# MCU.net
KiCad netlist of a schematic drawn in Altium Designer
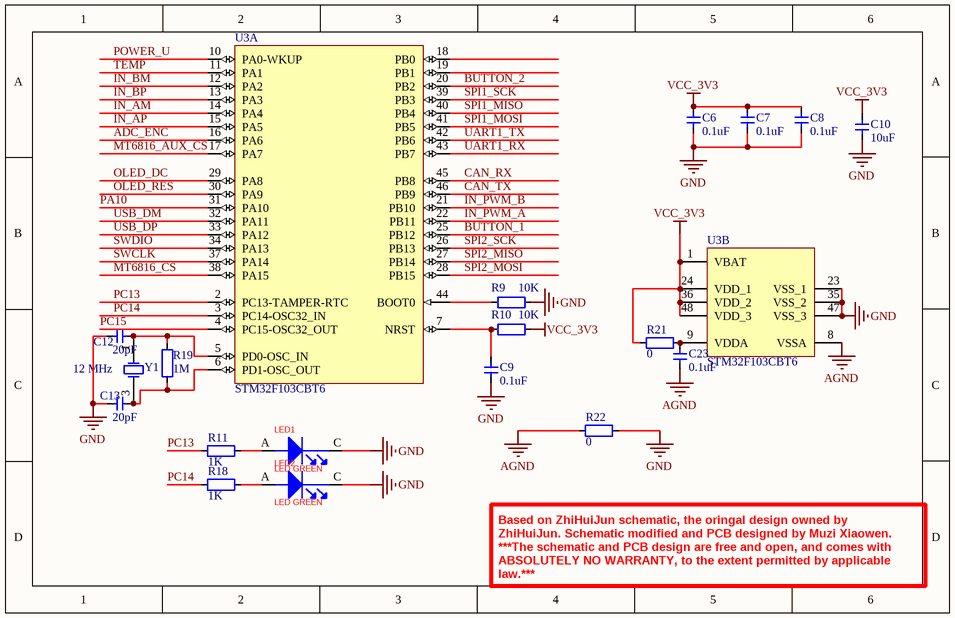
[diagram p0: MCU.SchDoc]

(export (version "E")
  (design (tool "Eeschema 10.0.6"))
  (components
    (comp (ref "C6")
      (value "0.1uF")
      (footprint "motor42-lib:CAP_0402")
      (description "Capacitor")
      (libsource (lib "MyPcbLib") (part "电容-0402"))
    )
    (comp (ref "C7")
      (value "0.1uF")
      (footprint "motor42-lib:CAP_0402")
      (description "Capacitor")
      (libsource (lib "MyPcbLib") (part "电容-0402"))
    )
    (comp (ref "C8")
      (value "0.1uF")
      (footprint "motor42-lib:CAP_0402")
      (description "Capacitor")
      (libsource (lib "MyPcbLib") (part "电容-0402"))
    )
    (comp (ref "C9")
      (value "0.1uF")
      (footprint "motor42-lib:CAP_0402")
      (description "Capacitor")
      (libsource (lib "MyPcbLib") (part "电容-0402"))
    )
    (comp (ref "C10")
      (value "10uF")
      (footprint "CAP_0402")
      (description "Capacitor")
      (libsource (lib "MyPcbLib") (part "电容-0402"))
    )
    (comp (ref "C12")
      (value "20pF")
      (footprint "motor42-lib:CAP_0402")
      (description "Capacitor")
      (libsource (lib "MyPcbLib") (part "电容-0402"))
    )
    (comp (ref "C13")
      (value "20pF")
      (footprint "motor42-lib:CAP_0402")
      (description "Capacitor")
      (libsource (lib "MyPcbLib") (part "电容-0402"))
    )
    (comp (ref "C23")
      (value "0.1uF")
      (footprint "motor42-lib:CAP_0402")
      (description "Capacitor")
      (libsource (lib "MyPcbLib") (part "电容-0402"))
    )
    (comp (ref "LED1")
      (value "LED GREEN")
      (footprint "LED-0603")
      (description "LED GRN SGL RA 25mA 4.1V SMD")
      (libsource (lib "*") (part "LED"))
    )
    (comp (ref "LED2")
      (value "LED GREEN")
      (footprint "LED-0603")
      (description "LED GRN SGL RA 25mA 4.1V SMD")
      (libsource (lib "*") (part "LED"))
    )
    (comp (ref "R9")
      (value "10K")
      (footprint "RES_0402")
      (description "Resistor")
      (libsource (lib "MyPcbLib") (part "电阻-0402"))
    )
    (comp (ref "R10")
      (value "10K")
      (footprint "RES_0402")
      (description "Resistor")
      (libsource (lib "MyPcbLib") (part "电阻-0402"))
    )
    (comp (ref "R11")
      (value "1K")
      (footprint "RES_0402")
      (description "Resistor")
      (libsource (lib "MyPcbLib") (part "电阻-0402"))
    )
    (comp (ref "R18")
      (value "1K")
      (footprint "RES_0402")
      (description "Resistor")
      (libsource (lib "MyPcbLib") (part "电阻-0402"))
    )
    (comp (ref "R19")
      (value "1M")
      (footprint "RES_0402")
      (description "Resistor")
      (libsource (lib "") (part "电阻-0402_2"))
    )
    (comp (ref "R21")
      (value "0")
      (footprint "RES_0402")
      (description "Resistor")
      (libsource (lib "") (part "电阻-0402_1"))
    )
    (comp (ref "R22")
      (value "0")
      (footprint "RES_0402")
      (description "Resistor")
      (libsource (lib "") (part "电阻-0402_1"))
    )
    (comp (ref "U3")
      (value "STM32F103CBT6")
      (footprint "motor42-lib:LQFP-48")
      (libsource (lib "STMicroelectronics STM32 F1") (part "STM32F103CBT6"))
    )
    (comp (ref "Y1")
      (value "12 MHz")
      (footprint "LC-SMD-3225_4P")
      (description "Crystal")
      (fields (field (name "Comment") "XTAL-4"))
      (libsource (lib "rpi") (part "XTAL-4"))
    )
  )
  (nets
    (net (code "1") (name "/ADC_ENC") (class "Default")
      (node (ref "U3") (pin "16") (pinfunction "PA6_16") (pintype "bidirectional"))
    )
    (net (code "2") (name "/BUTTON_1") (class "Default")
      (node (ref "U3") (pin "25") (pinfunction "PB12_25") (pintype "bidirectional"))
    )
    (net (code "3") (name "/BUTTON_2") (class "Default")
      (node (ref "U3") (pin "20") (pinfunction "PB2_20") (pintype "bidirectional"))
    )
    (net (code "4") (name "/CAN_RX") (class "Default")
      (node (ref "U3") (pin "45") (pinfunction "PB8_45") (pintype "bidirectional"))
    )
    (net (code "5") (name "/CAN_TX") (class "Default")
      (node (ref "U3") (pin "46") (pinfunction "PB9_46") (pintype "bidirectional"))
    )
    (net (code "6") (name "/IN_AM") (class "Default")
      (node (ref "U3") (pin "14") (pinfunction "PA4_14") (pintype "bidirectional"))
    )
    (net (code "7") (name "/IN_AP") (class "Default")
      (node (ref "U3") (pin "15") (pinfunction "PA5_15") (pintype "bidirectional"))
    )
    (net (code "8") (name "/IN_BM") (class "Default")
      (node (ref "U3") (pin "12") (pinfunction "PA2_12") (pintype "bidirectional"))
    )
    (net (code "9") (name "/IN_BP") (class "Default")
      (node (ref "U3") (pin "13") (pinfunction "PA3_13") (pintype "bidirectional"))
    )
    (net (code "10") (name "/IN_PWM_A") (class "Default")
      (node (ref "U3") (pin "22") (pinfunction "PB11_22") (pintype "bidirectional"))
    )
    (net (code "11") (name "/IN_PWM_B") (class "Default")
      (node (ref "U3") (pin "21") (pinfunction "PB10_21") (pintype "bidirectional"))
    )
    (net (code "12") (name "/MT6816_AUX_CS") (class "Default")
      (node (ref "U3") (pin "17") (pinfunction "PA7_17") (pintype "bidirectional"))
    )
    (net (code "13") (name "/MT6816_CS") (class "Default")
      (node (ref "U3") (pin "38") (pinfunction "PA15_38") (pintype "bidirectional"))
    )
    (net (code "14") (name "/OLED_DC") (class "Default")
      (node (ref "U3") (pin "29") (pinfunction "PA8_29") (pintype "bidirectional"))
    )
    (net (code "15") (name "/OLED_RES") (class "Default")
      (node (ref "U3") (pin "30") (pinfunction "PA9_30") (pintype "bidirectional"))
    )
    (net (code "16") (name "/PA10") (class "Default")
      (node (ref "U3") (pin "31") (pinfunction "PA10_31") (pintype "bidirectional"))
    )
    (net (code "17") (name "/PC13") (class "Default")
      (node (ref "R11") (pin "1") (pinfunction "1_1") (pintype "passive"))
      (node (ref "U3") (pin "2") (pinfunction "PC13-TAMPER-RTC_2") (pintype "bidirectional"))
    )
    (net (code "18") (name "/PC14") (class "Default")
      (node (ref "R18") (pin "1") (pinfunction "1_1") (pintype "passive"))
      (node (ref "U3") (pin "3") (pinfunction "PC14-OSC32_IN_3") (pintype "bidirectional"))
    )
    (net (code "19") (name "/PC15") (class "Default")
      (node (ref "U3") (pin "4") (pinfunction "PC15-OSC32_OUT_4") (pintype "bidirectional"))
    )
    (net (code "20") (name "/POWER_U") (class "Default")
      (node (ref "U3") (pin "10") (pinfunction "PA0-WKUP_10") (pintype "bidirectional"))
    )
    (net (code "21") (name "/SPI1_MISO") (class "Default")
      (node (ref "U3") (pin "40") (pinfunction "PB4_40") (pintype "bidirectional"))
    )
    (net (code "22") (name "/SPI1_MOSI") (class "Default")
      (node (ref "U3") (pin "41") (pinfunction "PB5_41") (pintype "bidirectional"))
    )
    (net (code "23") (name "/SPI1_SCK") (class "Default")
      (node (ref "U3") (pin "39") (pinfunction "PB3_39") (pintype "bidirectional"))
    )
    (net (code "24") (name "/SPI2_MISO") (class "Default")
      (node (ref "U3") (pin "27") (pinfunction "PB14_27") (pintype "bidirectional"))
    )
    (net (code "25") (name "/SPI2_MOSI") (class "Default")
      (node (ref "U3") (pin "28") (pinfunction "PB15_28") (pintype "bidirectional"))
    )
    (net (code "26") (name "/SPI2_SCK") (class "Default")
      (node (ref "U3") (pin "26") (pinfunction "PB13_26") (pintype "bidirectional"))
    )
    (net (code "27") (name "/SWCLK") (class "Default")
      (node (ref "U3") (pin "37") (pinfunction "PA14_37") (pintype "bidirectional"))
    )
    (net (code "28") (name "/SWDIO") (class "Default")
      (node (ref "U3") (pin "34") (pinfunction "PA13_34") (pintype "bidirectional"))
    )
    (net (code "29") (name "/TEMP") (class "Default")
      (node (ref "U3") (pin "11") (pinfunction "PA1_11") (pintype "bidirectional"))
    )
    (net (code "30") (name "/UART1_RX") (class "Default")
      (node (ref "U3") (pin "43") (pinfunction "PB7_43") (pintype "bidirectional"))
    )
    (net (code "31") (name "/UART1_TX") (class "Default")
      (node (ref "U3") (pin "42") (pinfunction "PB6_42") (pintype "bidirectional"))
    )
    (net (code "32") (name "/USB_DM") (class "Default")
      (node (ref "U3") (pin "32") (pinfunction "PA11_32") (pintype "bidirectional"))
    )
    (net (code "33") (name "/USB_DP") (class "Default")
      (node (ref "U3") (pin "33") (pinfunction "PA12_33") (pintype "bidirectional"))
    )
    (net (code "34") (name "AGND") (class "Default")
      (node (ref "C23") (pin "1") (pinfunction "1_1") (pintype "passive"))
      (node (ref "R22") (pin "2") (pinfunction "2_2") (pintype "passive"))
      (node (ref "U3") (pin "8") (pinfunction "VSSA_8") (pintype "power_in"))
    )
    (net (code "35") (name "GND") (class "Default")
      (node (ref "C10") (pin "1") (pinfunction "1_1") (pintype "passive"))
      (node (ref "C12") (pin "2") (pinfunction "2_2") (pintype "passive"))
      (node (ref "C13") (pin "2") (pinfunction "2_2") (pintype "passive"))
      (node (ref "C6") (pin "1") (pinfunction "1_1") (pintype "passive"))
      (node (ref "C7") (pin "1") (pinfunction "1_1") (pintype "passive"))
      (node (ref "C8") (pin "1") (pinfunction "1_1") (pintype "passive"))
      (node (ref "C9") (pin "1") (pinfunction "1_1") (pintype "passive"))
      (node (ref "LED1") (pin "C") (pinfunction "CATHODE_C") (pintype "passive"))
      (node (ref "LED2") (pin "C") (pinfunction "CATHODE_C") (pintype "passive"))
      (node (ref "R22") (pin "1") (pinfunction "1_1") (pintype "passive"))
      (node (ref "R9") (pin "2") (pinfunction "2_2") (pintype "passive"))
      (node (ref "U3") (pin "23") (pinfunction "VSS_1_23") (pintype "power_in"))
      (node (ref "U3") (pin "35") (pinfunction "VSS_2_35") (pintype "power_in"))
      (node (ref "U3") (pin "47") (pinfunction "VSS_3_47") (pintype "power_in"))
    )
    (net (code "36") (name "Net-(LED1-ANODE)") (class "Default")
      (node (ref "LED1") (pin "A") (pinfunction "ANODE_A") (pintype "passive"))
      (node (ref "R11") (pin "2") (pinfunction "2_2") (pintype "passive"))
    )
    (net (code "37") (name "Net-(LED2-ANODE)") (class "Default")
      (node (ref "LED2") (pin "A") (pinfunction "ANODE_A") (pintype "passive"))
      (node (ref "R18") (pin "2") (pinfunction "2_2") (pintype "passive"))
    )
    (net (code "38") (name "Net-(U3A-BOOT0)") (class "Default")
      (node (ref "R9") (pin "1") (pinfunction "1_1") (pintype "passive"))
      (node (ref "U3") (pin "44") (pinfunction "BOOT0_44") (pintype "input"))
    )
    (net (code "39") (name "Net-(U3A-NRST)") (class "Default")
      (node (ref "C9") (pin "2") (pinfunction "2_2") (pintype "passive"))
      (node (ref "R10") (pin "1") (pinfunction "1_1") (pintype "passive"))
      (node (ref "U3") (pin "7") (pinfunction "NRST_7") (pintype "bidirectional"))
    )
    (net (code "40") (name "Net-(U3A-PD0-OSC_IN)") (class "Default")
      (node (ref "C12") (pin "1") (pinfunction "1_1") (pintype "passive"))
      (node (ref "R19") (pin "2") (pinfunction "2_2") (pintype "passive"))
      (node (ref "U3") (pin "5") (pinfunction "PD0-OSC_IN_5") (pintype "bidirectional"))
      (node (ref "Y1") (pin "1") (pinfunction "OSC1_1") (pintype "passive"))
    )
    (net (code "41") (name "Net-(U3A-PD1-OSC_OUT)") (class "Default")
      (node (ref "C13") (pin "1") (pinfunction "1_1") (pintype "passive"))
      (node (ref "R19") (pin "1") (pinfunction "1_1") (pintype "passive"))
      (node (ref "U3") (pin "6") (pinfunction "PD1-OSC_OUT_6") (pintype "bidirectional"))
      (node (ref "Y1") (pin "3") (pinfunction "OSC2_3") (pintype "passive"))
    )
    (net (code "42") (name "Net-(U3B-VDDA)") (class "Default")
      (node (ref "C23") (pin "2") (pinfunction "2_2") (pintype "passive"))
      (node (ref "R21") (pin "1") (pinfunction "1_1") (pintype "passive"))
      (node (ref "U3") (pin "9") (pinfunction "VDDA_9") (pintype "power_in"))
    )
    (net (code "43") (name "VCC_3V3") (class "Default")
      (node (ref "C10") (pin "2") (pinfunction "2_2") (pintype "passive"))
      (node (ref "C6") (pin "2") (pinfunction "2_2") (pintype "passive"))
      (node (ref "C7") (pin "2") (pinfunction "2_2") (pintype "passive"))
      (node (ref "C8") (pin "2") (pinfunction "2_2") (pintype "passive"))
      (node (ref "R10") (pin "2") (pinfunction "2_2") (pintype "passive"))
      (node (ref "R21") (pin "2") (pinfunction "2_2") (pintype "passive"))
      (node (ref "U3") (pin "1") (pinfunction "VBAT_1") (pintype "power_in"))
      (node (ref "U3") (pin "24") (pinfunction "VDD_1_24") (pintype "power_in"))
      (node (ref "U3") (pin "36") (pinfunction "VDD_2_36") (pintype "power_in"))
      (node (ref "U3") (pin "48") (pinfunction "VDD_3_48") (pintype "power_in"))
    )
    (net (code "44") (name "unconnected-(U3A-PB0-Pad18)") (class "Default")
      (node (ref "U3") (pin "18") (pinfunction "PB0_18") (pintype "bidirectional"))
    )
    (net (code "45") (name "unconnected-(U3A-PB1-Pad19)") (class "Default")
      (node (ref "U3") (pin "19") (pinfunction "PB1_19") (pintype "bidirectional"))
    )
  )
)
